# 06_EXT_UART.net
KiCad netlist of a schematic drawn in Altium Designer
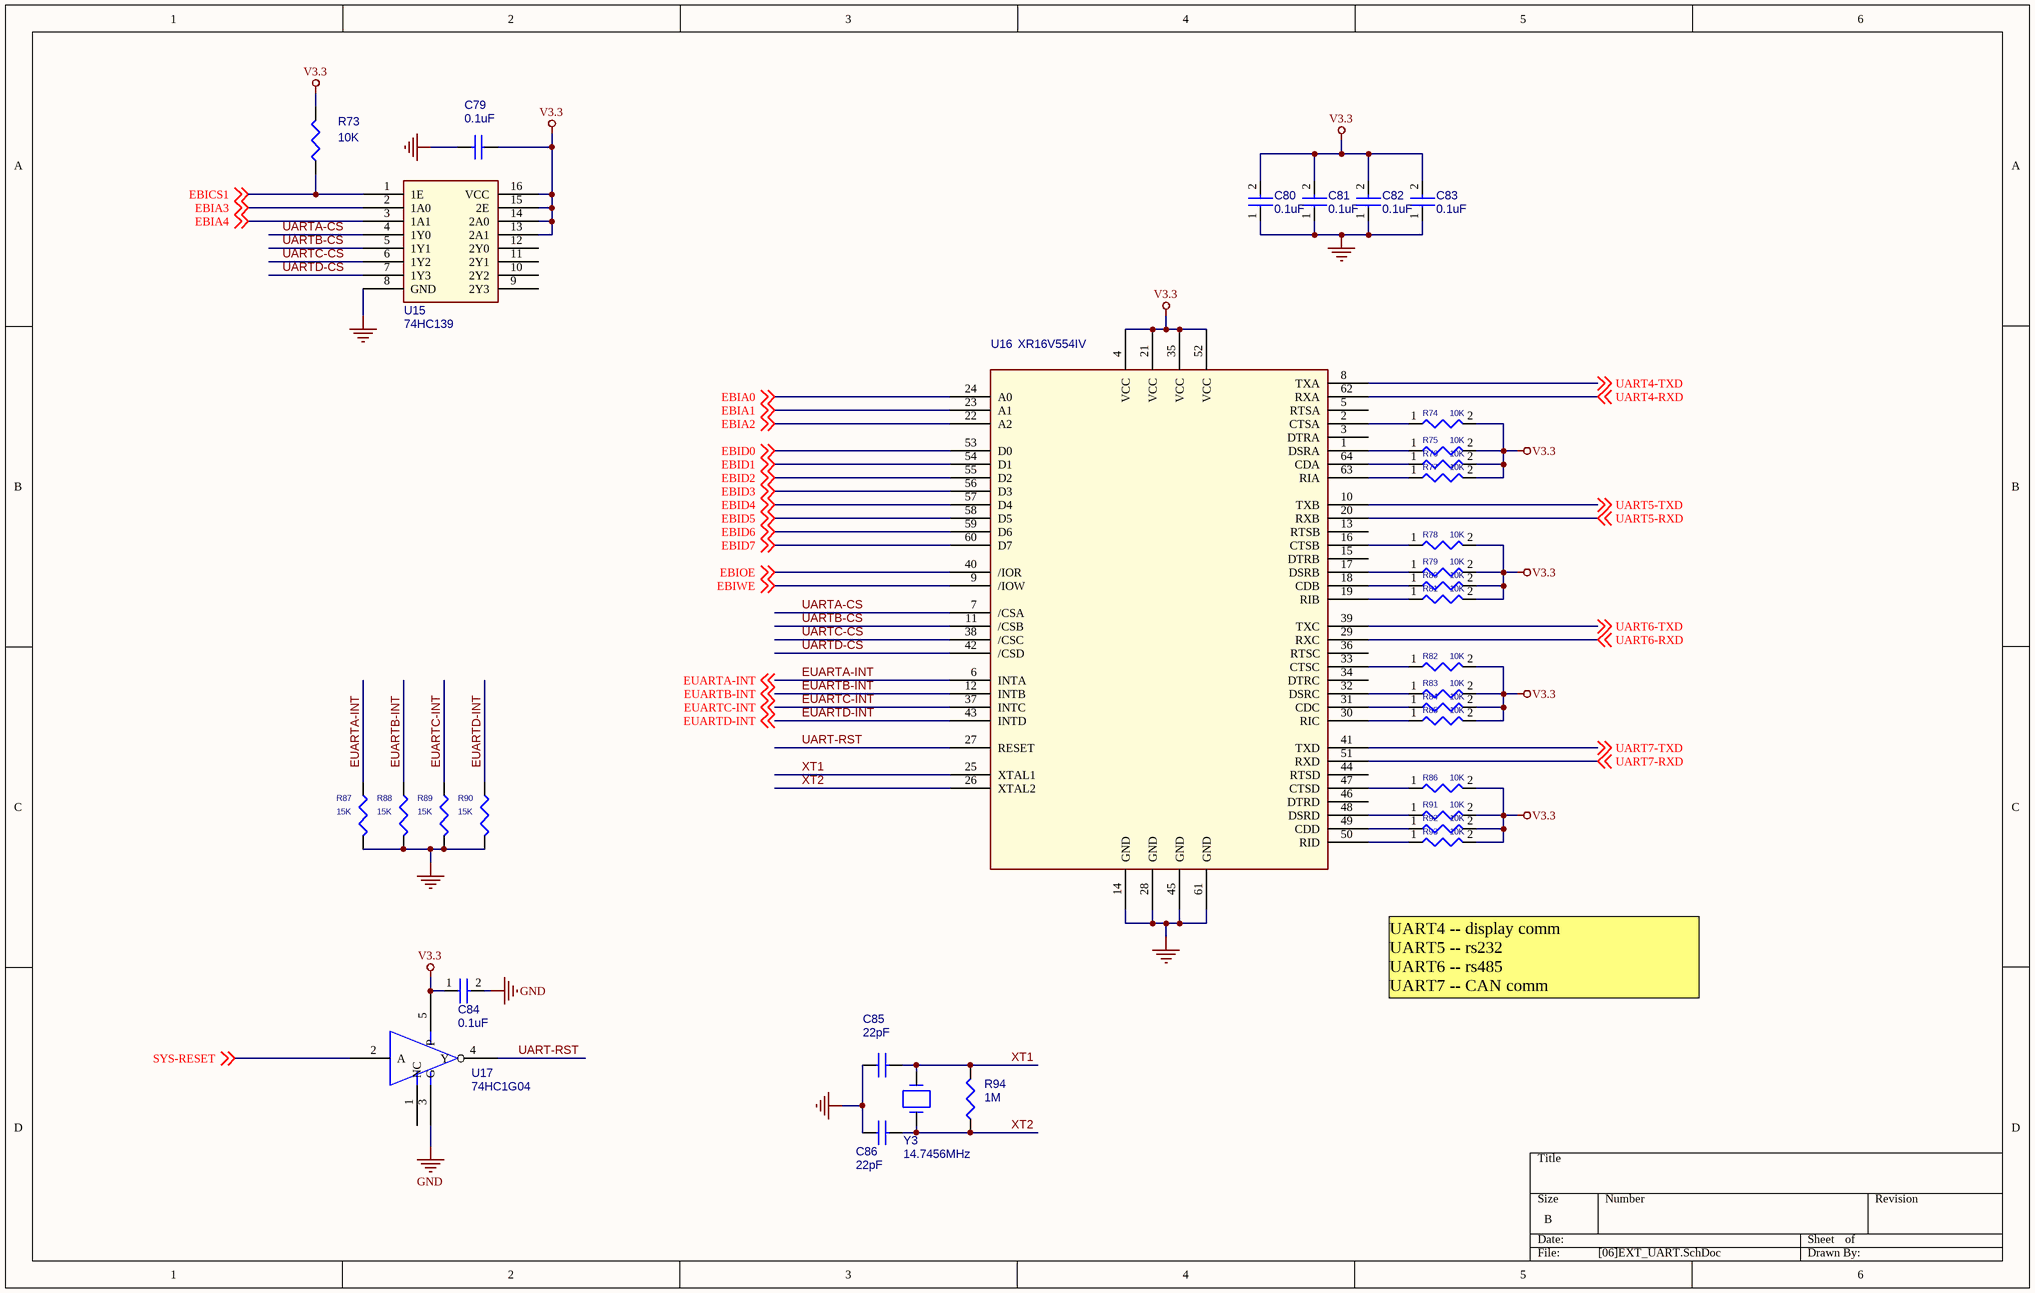
[diagram p0: [06]EXT_UART.SchDoc]

(export (version "E")
  (design (tool "Eeschema 10.0.6"))
  (components
    (comp (ref "C79") (value "0.1uF") (libsource (lib "") (part "CAP NP_Dup2_1")))
    (comp (ref "C80") (value "0.1uF") (libsource (lib "*") (part "CAP NP_Dup2")))
    (comp (ref "C81") (value "0.1uF") (libsource (lib "*") (part "CAP NP_Dup2")))
    (comp (ref "C82") (value "0.1uF") (libsource (lib "*") (part "CAP NP_Dup2")))
    (comp (ref "C83") (value "0.1uF") (libsource (lib "*") (part "CAP NP_Dup2")))
    (comp (ref "C84") (value "0.1uF") (footprint "0603") (libsource (lib "*") (part "CAP NP_Dup2")))
    (comp (ref "C85") (value "22pF") (libsource (lib "*") (part "CAP_Dup1")))
    (comp (ref "C86") (value "22pF") (libsource (lib "*") (part "CAP_Dup1")))
    (comp (ref "R73") (value "10K") (libsource (lib "*") (part "R_Dup1")))
    (comp (ref "R74") (value "10K") (libsource (lib "") (part "R_Dup1_1")))
    (comp (ref "R75") (value "10K") (libsource (lib "") (part "R_Dup1_1")))
    (comp (ref "R76") (value "10K") (libsource (lib "") (part "R_Dup1_1")))
    (comp (ref "R77") (value "10K") (libsource (lib "") (part "R_Dup1_1")))
    (comp (ref "R78") (value "10K") (libsource (lib "") (part "R_Dup1_1")))
    (comp (ref "R79") (value "10K") (libsource (lib "") (part "R_Dup1_1")))
    (comp (ref "R80") (value "10K") (libsource (lib "") (part "R_Dup1_1")))
    (comp (ref "R81") (value "10K") (libsource (lib "") (part "R_Dup1_1")))
    (comp (ref "R82") (value "10K") (libsource (lib "") (part "R_Dup1_1")))
    (comp (ref "R83") (value "10K") (libsource (lib "") (part "R_Dup1_1")))
    (comp (ref "R84") (value "10K") (libsource (lib "") (part "R_Dup1_1")))
    (comp (ref "R85") (value "10K") (libsource (lib "") (part "R_Dup1_1")))
    (comp (ref "R86") (value "10K") (libsource (lib "") (part "R_Dup1_1")))
    (comp (ref "R87") (value "15K") (libsource (lib "*") (part "R_Dup1")))
    (comp (ref "R88") (value "15K") (libsource (lib "*") (part "R_Dup1")))
    (comp (ref "R89") (value "15K") (libsource (lib "*") (part "R_Dup1")))
    (comp (ref "R90") (value "15K") (libsource (lib "*") (part "R_Dup1")))
    (comp (ref "R91") (value "10K") (libsource (lib "") (part "R_Dup1_1")))
    (comp (ref "R92") (value "10K") (libsource (lib "") (part "R_Dup1_1")))
    (comp (ref "R93") (value "10K") (libsource (lib "") (part "R_Dup1_1")))
    (comp (ref "R94") (value "1M") (libsource (lib "*") (part "RESISTOR")))
    (comp (ref "U15") (value "74HC139") (libsource (lib "*") (part "74HC139")))
    (comp (ref "U16") (value "XR16V554IV") (libsource (lib "*") (part "XR16V554IV_4")))
    (comp (ref "U17") (value "74HC1G04") (libsource (lib "*") (part "74LVC1G04GW_SOT353-5")))
    (comp (ref "Y3") (value "14.7456MHz") (libsource (lib "*") (part "CRYSTAL")))
  )
  (nets
    (net (code "1") (name "/UART-RST") (class "Default")
      (node (ref "U16") (pin "27") (pinfunction "RESET_27") (pintype "passive"))
      (node (ref "U17") (pin "4") (pinfunction "Y_4") (pintype "passive"))
    )
    (net (code "2") (name "/UARTA-CS") (class "Default")
      (node (ref "U15") (pin "4") (pinfunction "1Y0_4") (pintype "passive"))
      (node (ref "U16") (pin "7") (pinfunction "/CSA_7") (pintype "passive"))
    )
    (net (code "3") (name "/UARTB-CS") (class "Default")
      (node (ref "U15") (pin "5") (pinfunction "1Y1_5") (pintype "passive"))
      (node (ref "U16") (pin "11") (pinfunction "/CSB_11") (pintype "passive"))
    )
    (net (code "4") (name "/UARTC-CS") (class "Default")
      (node (ref "U15") (pin "6") (pinfunction "1Y2_6") (pintype "passive"))
      (node (ref "U16") (pin "38") (pinfunction "/CSC_38") (pintype "passive"))
    )
    (net (code "5") (name "/UARTD-CS") (class "Default")
      (node (ref "U15") (pin "7") (pinfunction "1Y3_7") (pintype "passive"))
      (node (ref "U16") (pin "42") (pinfunction "/CSD_42") (pintype "passive"))
    )
    (net (code "6") (name "/XT1") (class "Default")
      (node (ref "C85") (pin "2") (pinfunction "2_2") (pintype "passive"))
      (node (ref "R94") (pin "2") (pinfunction "2_2") (pintype "passive"))
      (node (ref "U16") (pin "25") (pinfunction "XTAL1_25") (pintype "passive"))
      (node (ref "Y3") (pin "2") (pinfunction "2_2") (pintype "passive"))
    )
    (net (code "7") (name "/XT2") (class "Default")
      (node (ref "C86") (pin "2") (pinfunction "2_2") (pintype "passive"))
      (node (ref "R94") (pin "1") (pinfunction "1_1") (pintype "passive"))
      (node (ref "U16") (pin "26") (pinfunction "XTAL2_26") (pintype "passive"))
      (node (ref "Y3") (pin "1") (pinfunction "1_1") (pintype "passive"))
    )
    (net (code "8") (name "EBIA0") (class "Default")
      (node (ref "U16") (pin "24") (pinfunction "A0_24") (pintype "passive"))
    )
    (net (code "9") (name "EBIA1") (class "Default")
      (node (ref "U16") (pin "23") (pinfunction "A1_23") (pintype "passive"))
    )
    (net (code "10") (name "EBIA2") (class "Default")
      (node (ref "U16") (pin "22") (pinfunction "A2_22") (pintype "passive"))
    )
    (net (code "11") (name "EBIA3") (class "Default")
      (node (ref "U15") (pin "2") (pinfunction "1A0_2") (pintype "passive"))
    )
    (net (code "12") (name "EBIA4") (class "Default")
      (node (ref "U15") (pin "3") (pinfunction "1A1_3") (pintype "passive"))
    )
    (net (code "13") (name "EBICS1") (class "Default")
      (node (ref "R73") (pin "1") (pinfunction "1_1") (pintype "passive"))
      (node (ref "U15") (pin "1") (pinfunction "1E_1") (pintype "passive"))
    )
    (net (code "14") (name "EBID0") (class "Default")
      (node (ref "U16") (pin "53") (pinfunction "D0_53") (pintype "passive"))
    )
    (net (code "15") (name "EBID1") (class "Default")
      (node (ref "U16") (pin "54") (pinfunction "D1_54") (pintype "passive"))
    )
    (net (code "16") (name "EBID2") (class "Default")
      (node (ref "U16") (pin "55") (pinfunction "D2_55") (pintype "passive"))
    )
    (net (code "17") (name "EBID3") (class "Default")
      (node (ref "U16") (pin "56") (pinfunction "D3_56") (pintype "passive"))
    )
    (net (code "18") (name "EBID4") (class "Default")
      (node (ref "U16") (pin "57") (pinfunction "D4_57") (pintype "passive"))
    )
    (net (code "19") (name "EBID5") (class "Default")
      (node (ref "U16") (pin "58") (pinfunction "D5_58") (pintype "passive"))
    )
    (net (code "20") (name "EBID6") (class "Default")
      (node (ref "U16") (pin "59") (pinfunction "D6_59") (pintype "passive"))
    )
    (net (code "21") (name "EBID7") (class "Default")
      (node (ref "U16") (pin "60") (pinfunction "D7_60") (pintype "passive"))
    )
    (net (code "22") (name "EBIOE") (class "Default")
      (node (ref "U16") (pin "40") (pinfunction "/IOR_40") (pintype "passive"))
    )
    (net (code "23") (name "EBIWE") (class "Default")
      (node (ref "U16") (pin "9") (pinfunction "/IOW_9") (pintype "passive"))
    )
    (net (code "24") (name "EUARTA-INT") (class "Default")
      (node (ref "R87") (pin "1") (pinfunction "1_1") (pintype "passive"))
      (node (ref "U16") (pin "6") (pinfunction "INTA_6") (pintype "passive"))
    )
    (net (code "25") (name "EUARTB-INT") (class "Default")
      (node (ref "R88") (pin "1") (pinfunction "1_1") (pintype "passive"))
      (node (ref "U16") (pin "12") (pinfunction "INTB_12") (pintype "passive"))
    )
    (net (code "26") (name "EUARTC-INT") (class "Default")
      (node (ref "R89") (pin "1") (pinfunction "1_1") (pintype "passive"))
      (node (ref "U16") (pin "37") (pinfunction "INTC_37") (pintype "passive"))
    )
    (net (code "27") (name "EUARTD-INT") (class "Default")
      (node (ref "R90") (pin "1") (pinfunction "1_1") (pintype "passive"))
      (node (ref "U16") (pin "43") (pinfunction "INTD_43") (pintype "passive"))
    )
    (net (code "28") (name "GND") (class "Default")
      (node (ref "C79") (pin "2") (pinfunction "2_2") (pintype "passive"))
      (node (ref "C80") (pin "1") (pinfunction "1_1") (pintype "passive"))
      (node (ref "C81") (pin "1") (pinfunction "1_1") (pintype "passive"))
      (node (ref "C82") (pin "1") (pinfunction "1_1") (pintype "passive"))
      (node (ref "C83") (pin "1") (pinfunction "1_1") (pintype "passive"))
      (node (ref "C84") (pin "2") (pinfunction "2_2") (pintype "passive"))
      (node (ref "C85") (pin "1") (pinfunction "1_1") (pintype "passive"))
      (node (ref "C86") (pin "1") (pinfunction "1_1") (pintype "passive"))
      (node (ref "R87") (pin "2") (pinfunction "2_2") (pintype "passive"))
      (node (ref "R88") (pin "2") (pinfunction "2_2") (pintype "passive"))
      (node (ref "R89") (pin "2") (pinfunction "2_2") (pintype "passive"))
      (node (ref "R90") (pin "2") (pinfunction "2_2") (pintype "passive"))
      (node (ref "U15") (pin "8") (pinfunction "GND_8") (pintype "passive"))
      (node (ref "U16") (pin "14") (pinfunction "GND_14") (pintype "power_in"))
      (node (ref "U16") (pin "28") (pinfunction "GND_28") (pintype "power_in"))
      (node (ref "U16") (pin "45") (pinfunction "GND_45") (pintype "power_in"))
      (node (ref "U16") (pin "61") (pinfunction "GND_61") (pintype "power_in"))
      (node (ref "U17") (pin "3") (pinfunction "G_3") (pintype "passive"))
    )
    (net (code "29") (name "Net-(U16-CDA)") (class "Default")
      (node (ref "R76") (pin "1") (pinfunction "1_1") (pintype "passive"))
      (node (ref "U16") (pin "64") (pinfunction "CDA_64") (pintype "passive"))
    )
    (net (code "30") (name "Net-(U16-CDB)") (class "Default")
      (node (ref "R80") (pin "1") (pinfunction "1_1") (pintype "passive"))
      (node (ref "U16") (pin "18") (pinfunction "CDB_18") (pintype "passive"))
    )
    (net (code "31") (name "Net-(U16-CDC)") (class "Default")
      (node (ref "R84") (pin "1") (pinfunction "1_1") (pintype "passive"))
      (node (ref "U16") (pin "31") (pinfunction "CDC_31") (pintype "passive"))
    )
    (net (code "32") (name "Net-(U16-CDD)") (class "Default")
      (node (ref "R92") (pin "1") (pinfunction "1_1") (pintype "passive"))
      (node (ref "U16") (pin "49") (pinfunction "CDD_49") (pintype "passive"))
    )
    (net (code "33") (name "Net-(U16-CTSA)") (class "Default")
      (node (ref "R74") (pin "1") (pinfunction "1_1") (pintype "passive"))
      (node (ref "U16") (pin "2") (pinfunction "CTSA_2") (pintype "passive"))
    )
    (net (code "34") (name "Net-(U16-CTSB)") (class "Default")
      (node (ref "R78") (pin "1") (pinfunction "1_1") (pintype "passive"))
      (node (ref "U16") (pin "16") (pinfunction "CTSB_16") (pintype "passive"))
    )
    (net (code "35") (name "Net-(U16-CTSC)") (class "Default")
      (node (ref "R82") (pin "1") (pinfunction "1_1") (pintype "passive"))
      (node (ref "U16") (pin "33") (pinfunction "CTSC_33") (pintype "passive"))
    )
    (net (code "36") (name "Net-(U16-CTSD)") (class "Default")
      (node (ref "R86") (pin "1") (pinfunction "1_1") (pintype "passive"))
      (node (ref "U16") (pin "47") (pinfunction "CTSD_47") (pintype "passive"))
    )
    (net (code "37") (name "Net-(U16-DSRA)") (class "Default")
      (node (ref "R75") (pin "1") (pinfunction "1_1") (pintype "passive"))
      (node (ref "U16") (pin "1") (pinfunction "DSRA_1") (pintype "passive"))
    )
    (net (code "38") (name "Net-(U16-DSRB)") (class "Default")
      (node (ref "R79") (pin "1") (pinfunction "1_1") (pintype "passive"))
      (node (ref "U16") (pin "17") (pinfunction "DSRB_17") (pintype "passive"))
    )
    (net (code "39") (name "Net-(U16-DSRC)") (class "Default")
      (node (ref "R83") (pin "1") (pinfunction "1_1") (pintype "passive"))
      (node (ref "U16") (pin "32") (pinfunction "DSRC_32") (pintype "passive"))
    )
    (net (code "40") (name "Net-(U16-DSRD)") (class "Default")
      (node (ref "R91") (pin "1") (pinfunction "1_1") (pintype "passive"))
      (node (ref "U16") (pin "48") (pinfunction "DSRD_48") (pintype "passive"))
    )
    (net (code "41") (name "Net-(U16-RIA)") (class "Default")
      (node (ref "R77") (pin "1") (pinfunction "1_1") (pintype "passive"))
      (node (ref "U16") (pin "63") (pinfunction "RIA_63") (pintype "passive"))
    )
    (net (code "42") (name "Net-(U16-RIB)") (class "Default")
      (node (ref "R81") (pin "1") (pinfunction "1_1") (pintype "passive"))
      (node (ref "U16") (pin "19") (pinfunction "RIB_19") (pintype "passive"))
    )
    (net (code "43") (name "Net-(U16-RIC)") (class "Default")
      (node (ref "R85") (pin "1") (pinfunction "1_1") (pintype "passive"))
      (node (ref "U16") (pin "30") (pinfunction "RIC_30") (pintype "passive"))
    )
    (net (code "44") (name "Net-(U16-RID)") (class "Default")
      (node (ref "R93") (pin "1") (pinfunction "1_1") (pintype "passive"))
      (node (ref "U16") (pin "50") (pinfunction "RID_50") (pintype "passive"))
    )
    (net (code "45") (name "SYS-RESET") (class "Default")
      (node (ref "U17") (pin "2") (pinfunction "A_2") (pintype "passive"))
    )
    (net (code "46") (name "UART4-RXD") (class "Default")
      (node (ref "U16") (pin "62") (pinfunction "RXA_62") (pintype "passive"))
    )
    (net (code "47") (name "UART4-TXD") (class "Default")
      (node (ref "U16") (pin "8") (pinfunction "TXA_8") (pintype "passive"))
    )
    (net (code "48") (name "UART5-RXD") (class "Default")
      (node (ref "U16") (pin "20") (pinfunction "RXB_20") (pintype "passive"))
    )
    (net (code "49") (name "UART5-TXD") (class "Default")
      (node (ref "U16") (pin "10") (pinfunction "TXB_10") (pintype "passive"))
    )
    (net (code "50") (name "UART6-RXD") (class "Default")
      (node (ref "U16") (pin "29") (pinfunction "RXC_29") (pintype "passive"))
    )
    (net (code "51") (name "UART6-TXD") (class "Default")
      (node (ref "U16") (pin "39") (pinfunction "TXC_39") (pintype "passive"))
    )
    (net (code "52") (name "UART7-RXD") (class "Default")
      (node (ref "U16") (pin "51") (pinfunction "RXD_51") (pintype "passive"))
    )
    (net (code "53") (name "UART7-TXD") (class "Default")
      (node (ref "U16") (pin "41") (pinfunction "TXD_41") (pintype "passive"))
    )
    (net (code "54") (name "V3.3") (class "Default")
      (node (ref "C79") (pin "1") (pinfunction "1_1") (pintype "passive"))
      (node (ref "C80") (pin "2") (pinfunction "2_2") (pintype "passive"))
      (node (ref "C81") (pin "2") (pinfunction "2_2") (pintype "passive"))
      (node (ref "C82") (pin "2") (pinfunction "2_2") (pintype "passive"))
      (node (ref "C83") (pin "2") (pinfunction "2_2") (pintype "passive"))
      (node (ref "C84") (pin "1") (pinfunction "1_1") (pintype "passive"))
      (node (ref "R73") (pin "2") (pinfunction "2_2") (pintype "passive"))
      (node (ref "R74") (pin "2") (pinfunction "2_2") (pintype "passive"))
      (node (ref "R75") (pin "2") (pinfunction "2_2") (pintype "passive"))
      (node (ref "R76") (pin "2") (pinfunction "2_2") (pintype "passive"))
      (node (ref "R77") (pin "2") (pinfunction "2_2") (pintype "passive"))
      (node (ref "R78") (pin "2") (pinfunction "2_2") (pintype "passive"))
      (node (ref "R79") (pin "2") (pinfunction "2_2") (pintype "passive"))
      (node (ref "R80") (pin "2") (pinfunction "2_2") (pintype "passive"))
      (node (ref "R81") (pin "2") (pinfunction "2_2") (pintype "passive"))
      (node (ref "R82") (pin "2") (pinfunction "2_2") (pintype "passive"))
      (node (ref "R83") (pin "2") (pinfunction "2_2") (pintype "passive"))
      (node (ref "R84") (pin "2") (pinfunction "2_2") (pintype "passive"))
      (node (ref "R85") (pin "2") (pinfunction "2_2") (pintype "passive"))
      (node (ref "R86") (pin "2") (pinfunction "2_2") (pintype "passive"))
      (node (ref "R91") (pin "2") (pinfunction "2_2") (pintype "passive"))
      (node (ref "R92") (pin "2") (pinfunction "2_2") (pintype "passive"))
      (node (ref "R93") (pin "2") (pinfunction "2_2") (pintype "passive"))
      (node (ref "U15") (pin "13") (pinfunction "2A1_13") (pintype "passive"))
      (node (ref "U15") (pin "14") (pinfunction "2A0_14") (pintype "passive"))
      (node (ref "U15") (pin "15") (pinfunction "2E_15") (pintype "passive"))
      (node (ref "U15") (pin "16") (pinfunction "VCC_16") (pintype "passive"))
      (node (ref "U16") (pin "21") (pinfunction "VCC_21") (pintype "power_in"))
      (node (ref "U16") (pin "35") (pinfunction "VCC_35") (pintype "power_in"))
      (node (ref "U16") (pin "4") (pinfunction "VCC_4") (pintype "power_in"))
      (node (ref "U16") (pin "52") (pinfunction "VCC_52") (pintype "power_in"))
      (node (ref "U17") (pin "5") (pinfunction "P_5") (pintype "passive"))
    )
    (net (code "55") (name "unconnected-(U15-2Y0-Pad12)") (class "Default")
      (node (ref "U15") (pin "12") (pinfunction "2Y0_12") (pintype "passive"))
    )
    (net (code "56") (name "unconnected-(U15-2Y1-Pad11)") (class "Default")
      (node (ref "U15") (pin "11") (pinfunction "2Y1_11") (pintype "passive"))
    )
    (net (code "57") (name "unconnected-(U15-2Y2-Pad10)") (class "Default")
      (node (ref "U15") (pin "10") (pinfunction "2Y2_10") (pintype "passive"))
    )
    (net (code "58") (name "unconnected-(U15-2Y3-Pad9)") (class "Default")
      (node (ref "U15") (pin "9") (pinfunction "2Y3_9") (pintype "passive"))
    )
    (net (code "59") (name "unconnected-(U16-DTRA-Pad3)") (class "Default")
      (node (ref "U16") (pin "3") (pinfunction "DTRA_3") (pintype "passive"))
    )
    (net (code "60") (name "unconnected-(U16-DTRB-Pad15)") (class "Default")
      (node (ref "U16") (pin "15") (pinfunction "DTRB_15") (pintype "passive"))
    )
    (net (code "61") (name "unconnected-(U16-DTRC-Pad34)") (class "Default")
      (node (ref "U16") (pin "34") (pinfunction "DTRC_34") (pintype "passive"))
    )
    (net (code "62") (name "unconnected-(U16-DTRD-Pad46)") (class "Default")
      (node (ref "U16") (pin "46") (pinfunction "DTRD_46") (pintype "passive"))
    )
    (net (code "63") (name "unconnected-(U16-RTSA-Pad5)") (class "Default")
      (node (ref "U16") (pin "5") (pinfunction "RTSA_5") (pintype "passive"))
    )
    (net (code "64") (name "unconnected-(U16-RTSB-Pad13)") (class "Default")
      (node (ref "U16") (pin "13") (pinfunction "RTSB_13") (pintype "passive"))
    )
    (net (code "65") (name "unconnected-(U16-RTSC-Pad36)") (class "Default")
      (node (ref "U16") (pin "36") (pinfunction "RTSC_36") (pintype "passive"))
    )
    (net (code "66") (name "unconnected-(U16-RTSD-Pad44)") (class "Default")
      (node (ref "U16") (pin "44") (pinfunction "RTSD_44") (pintype "passive"))
    )
    (net (code "67") (name "unconnected-(U17-NC-Pad1)") (class "Default")
      (node (ref "U17") (pin "1") (pinfunction "NC_1") (pintype "passive"))
    )
  )
)
